# Power_Input_and_Regulators.net
KiCad netlist of a schematic drawn in Altium Designer
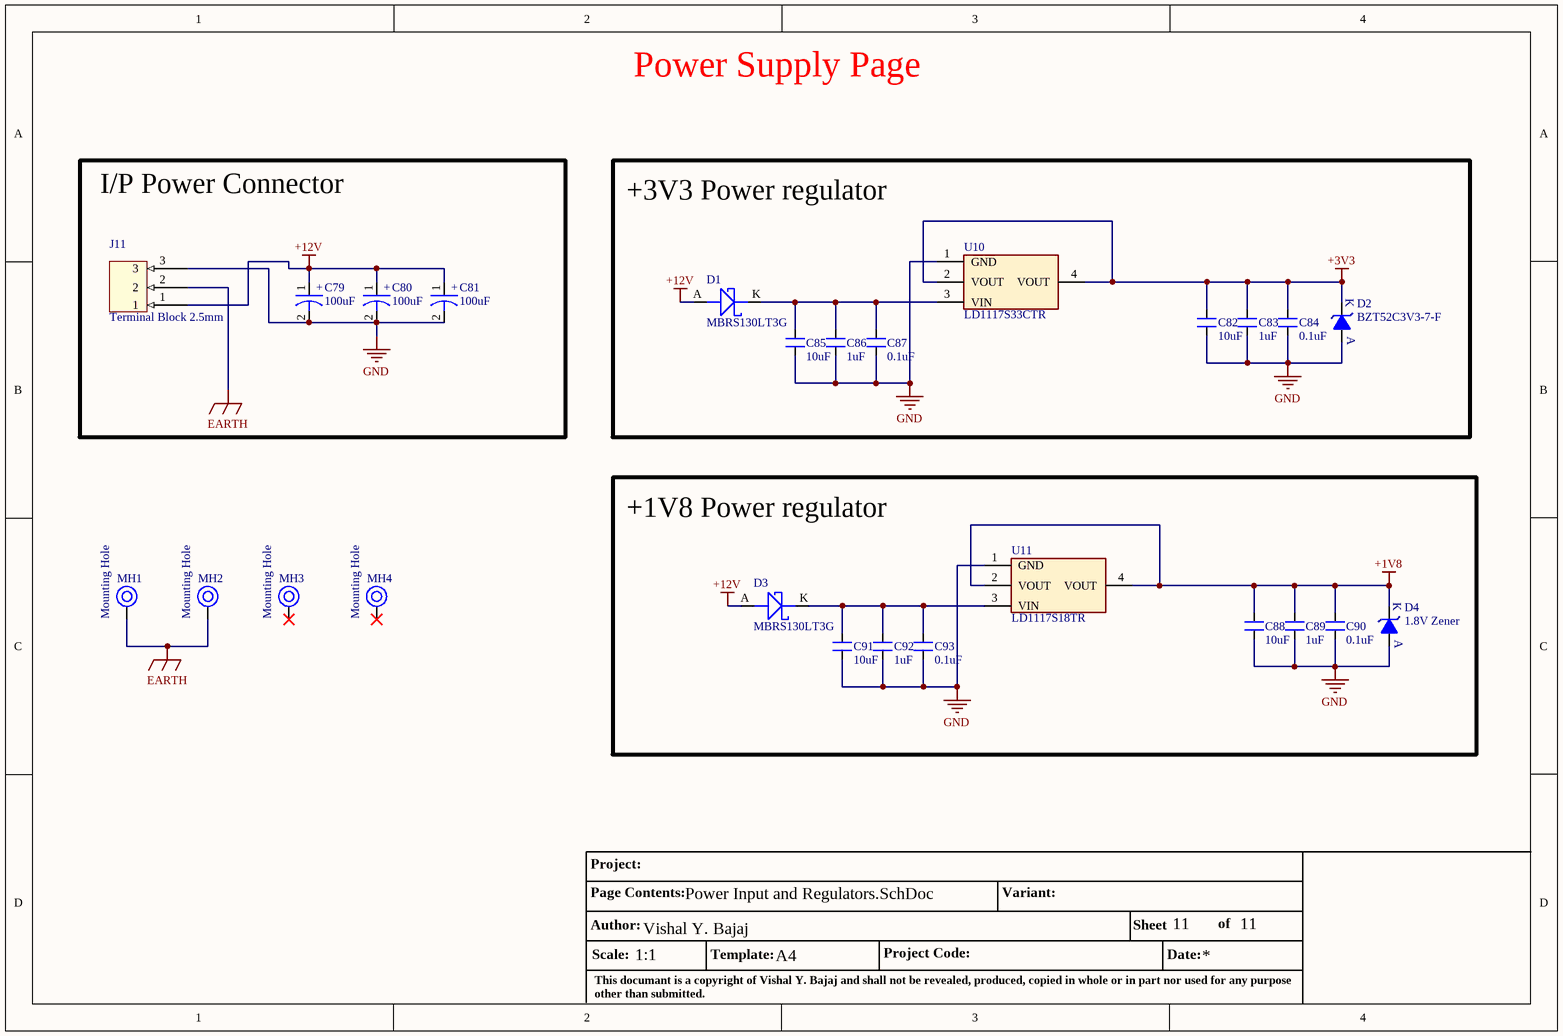
[diagram p0: Power Input and Regulators.SchDoc]

(export (version "E")
  (design (tool "Eeschema 10.0.6"))
  (components
    (comp (ref "C79")
      (value "100uF")
      (footprint "ACAP_P305_D393_H393_RAD")
      (description "100µF 50V Aluminum Polymer Capacitor Radial, Can - SMD 28mOhm 4000 Hrs @ 125°C")
      (fields
        (field (name "MANUFACTURER") "Nichicon")
        (field (name "MANUFACTURER PART NUMBER") "GYA1H101MCQ1GS")
      )
      (libsource (lib "ESTEEMPCBLIB") (part "CAP-P_100uF-50V-20%-RAD"))
    )
    (comp (ref "C80")
      (value "100uF")
      (footprint "ACAP_P305_D393_H393_RAD")
      (description "100µF 50V Aluminum Polymer Capacitor Radial, Can - SMD 28mOhm 4000 Hrs @ 125°C")
      (fields
        (field (name "MANUFACTURER") "Nichicon")
        (field (name "MANUFACTURER PART NUMBER") "GYA1H101MCQ1GS")
      )
      (libsource (lib "ESTEEMPCBLIB") (part "CAP-P_100uF-50V-20%-RAD"))
    )
    (comp (ref "C81")
      (value "100uF")
      (footprint "ACAP_P305_D393_H393_RAD")
      (description "100µF 50V Aluminum Polymer Capacitor Radial, Can - SMD 28mOhm 4000 Hrs @ 125°C")
      (fields
        (field (name "MANUFACTURER") "Nichicon")
        (field (name "MANUFACTURER PART NUMBER") "GYA1H101MCQ1GS")
      )
      (libsource (lib "ESTEEMPCBLIB") (part "CAP-P_100uF-50V-20%-RAD"))
    )
    (comp (ref "C82")
      (value "10uF")
      (footprint "CAP_1206")
      (description "10µF ±10% 50V Ceramic Capacitor X7R 1206 (3216 Metric)")
      (fields
        (field (name "MANUFACTURER") "KEMET")
        (field (name "MANUFACTURER PART NUMBER") "CL31B106KBHNNNE")
      )
      (libsource (lib "ESTEEMPCBLIB") (part "CAP_10uF-50V-10%-1206"))
    )
    (comp (ref "C83")
      (value "1uF")
      (footprint "CAP_0805")
      (description "1µF ±5% 50V Ceramic Capacitor X7R 0805 (2012 Metric)")
      (fields
        (field (name "MANUFACTURER") "Samsung")
        (field (name "MANUFACTURER PART NUMBER") "CC0805JKX7R9BB105")
      )
      (libsource (lib "ESTEEMPCBLIB") (part "CAP_1uF-50V-5%-0805"))
    )
    (comp (ref "C84")
      (value "0.1uF")
      (footprint "CAP_0805")
      (description "0.1µF ±10% 50V Ceramic Capacitor X7R 0805 (2012 Metric)")
      (fields
        (field (name "MANUFACTURER") "Samsung")
        (field (name "MANUFACTURER PART NUMBER") "CL21B104KBCNNNC")
      )
      (libsource (lib "ESTEEMPCBLIB") (part "CAP_0.1uF-50V-10%-0805"))
    )
    (comp (ref "C85")
      (value "10uF")
      (footprint "CAP_1206")
      (description "10µF ±10% 50V Ceramic Capacitor X7R 1206 (3216 Metric)")
      (fields
        (field (name "MANUFACTURER") "KEMET")
        (field (name "MANUFACTURER PART NUMBER") "CL31B106KBHNNNE")
      )
      (libsource (lib "ESTEEMPCBLIB") (part "CAP_10uF-50V-10%-1206"))
    )
    (comp (ref "C86")
      (value "1uF")
      (footprint "CAP_0805")
      (description "1µF ±5% 50V Ceramic Capacitor X7R 0805 (2012 Metric)")
      (fields
        (field (name "MANUFACTURER") "Samsung")
        (field (name "MANUFACTURER PART NUMBER") "CC0805JKX7R9BB105")
      )
      (libsource (lib "ESTEEMPCBLIB") (part "CAP_1uF-50V-5%-0805"))
    )
    (comp (ref "C87")
      (value "0.1uF")
      (footprint "CAP_0805")
      (description "0.1µF ±10% 50V Ceramic Capacitor X7R 0805 (2012 Metric)")
      (fields
        (field (name "MANUFACTURER") "Samsung")
        (field (name "MANUFACTURER PART NUMBER") "CL21B104KBCNNNC")
      )
      (libsource (lib "ESTEEMPCBLIB") (part "CAP_0.1uF-50V-10%-0805"))
    )
    (comp (ref "C88")
      (value "10uF")
      (footprint "CAP_1206")
      (description "10µF ±10% 50V Ceramic Capacitor X7R 1206 (3216 Metric)")
      (fields
        (field (name "MANUFACTURER") "KEMET")
        (field (name "MANUFACTURER PART NUMBER") "CL31B106KBHNNNE")
      )
      (libsource (lib "ESTEEMPCBLIB") (part "CAP_10uF-50V-10%-1206"))
    )
    (comp (ref "C89")
      (value "1uF")
      (footprint "CAP_0805")
      (description "1µF ±5% 50V Ceramic Capacitor X7R 0805 (2012 Metric)")
      (fields
        (field (name "MANUFACTURER") "Samsung")
        (field (name "MANUFACTURER PART NUMBER") "CC0805JKX7R9BB105")
      )
      (libsource (lib "ESTEEMPCBLIB") (part "CAP_1uF-50V-5%-0805"))
    )
    (comp (ref "C90")
      (value "0.1uF")
      (footprint "CAP_0805")
      (description "0.1µF ±10% 50V Ceramic Capacitor X7R 0805 (2012 Metric)")
      (fields
        (field (name "MANUFACTURER") "Samsung")
        (field (name "MANUFACTURER PART NUMBER") "CL21B104KBCNNNC")
      )
      (libsource (lib "ESTEEMPCBLIB") (part "CAP_0.1uF-50V-10%-0805"))
    )
    (comp (ref "C91")
      (value "10uF")
      (footprint "CAP_1206")
      (description "10µF ±10% 50V Ceramic Capacitor X7R 1206 (3216 Metric)")
      (fields
        (field (name "MANUFACTURER") "KEMET")
        (field (name "MANUFACTURER PART NUMBER") "CL31B106KBHNNNE")
      )
      (libsource (lib "ESTEEMPCBLIB") (part "CAP_10uF-50V-10%-1206"))
    )
    (comp (ref "C92")
      (value "1uF")
      (footprint "CAP_0805")
      (description "1µF ±5% 50V Ceramic Capacitor X7R 0805 (2012 Metric)")
      (fields
        (field (name "MANUFACTURER") "Samsung")
        (field (name "MANUFACTURER PART NUMBER") "CC0805JKX7R9BB105")
      )
      (libsource (lib "ESTEEMPCBLIB") (part "CAP_1uF-50V-5%-0805"))
    )
    (comp (ref "C93")
      (value "0.1uF")
      (footprint "CAP_0805")
      (description "0.1µF ±10% 50V Ceramic Capacitor X7R 0805 (2012 Metric)")
      (fields
        (field (name "MANUFACTURER") "Samsung")
        (field (name "MANUFACTURER PART NUMBER") "CL21B104KBCNNNC")
      )
      (libsource (lib "ESTEEMPCBLIB") (part "CAP_0.1uF-50V-10%-0805"))
    )
    (comp (ref "D1")
      (value "MBRS130LT3G")
      (footprint "DIO_SMB_DO-214AA")
      (description "Diode Schottky 30V 2A Surface Mount SMB")
      (fields (field (name "MANUFACTURER") "ON Semiconductor"))
      (libsource (lib "ESTEEMPCBLIB") (part "DIO-S_445mV-30V-2A-SMB"))
    )
    (comp (ref "D2")
      (value "BZT52C3V3-7-F")
      (footprint "DIO_SOD-123")
      (description "Zener Diode 3.3V 500mW ±6% Surface Mount SOD-123")
      (fields (field (name "MANUFACTURER") "Diodes Incorporated"))
      (libsource (lib "ESTEEMPCBLIB") (part "DIO-Z_3.3V-500mW-SOD123"))
    )
    (comp (ref "D3")
      (value "MBRS130LT3G")
      (footprint "DIO_SMB_DO-214AA")
      (description "Diode Schottky 30V 2A Surface Mount SMB")
      (fields (field (name "MANUFACTURER") "ON Semiconductor"))
      (libsource (lib "ESTEEMPCBLIB") (part "DIO-S_445mV-30V-2A-SMB"))
    )
    (comp (ref "D4")
      (value "1.8V Zener")
      (footprint "DIO_DO-213AB_SMD")
      (description "Zener Diode 1.8V 500mW ±5% Surface Mount DO-213AA")
      (libsource (lib "ESTEEMPCBLIB") (part "DIO-Z_1.8V-500mW-DO213AA"))
    )
    (comp (ref "J11")
      (value "Terminal Block 2.5mm")
      (footprint "CON3_100_TB_TH_ST")
      (description "3 Pins, 1 Row 2.54mm Pitch, straight Connector, male")
      (fields
        (field (name "MANUFACTURER PART NUMBER") "1725669")
        (field (name "MANUFACTURER") "Phoenix Contact")
      )
      (libsource (lib "ESTEEMPCBLIB") (part "CON-TB_3X1-100-ST-TH"))
    )
    (comp (ref "MH1")
      (value "Mounting Hole")
      (footprint "MOUNTING")
      (fields (field (name "MANUFACTURER PART NUMBER") "NA"))
      (libsource (lib "ESTEEMPCBLIB") (part "MH_3.5H_6D"))
    )
    (comp (ref "MH2")
      (value "Mounting Hole")
      (footprint "MOUNTING")
      (fields (field (name "MANUFACTURER PART NUMBER") "NA"))
      (libsource (lib "ESTEEMPCBLIB") (part "MH_3.5H_6D"))
    )
    (comp (ref "MH3")
      (value "Mounting Hole")
      (footprint "MOUNTING")
      (fields (field (name "MANUFACTURER PART NUMBER") "NA"))
      (libsource (lib "ESTEEMPCBLIB") (part "MH_3.5H_6D"))
    )
    (comp (ref "MH4")
      (value "Mounting Hole")
      (footprint "MOUNTING")
      (fields (field (name "MANUFACTURER PART NUMBER") "NA"))
      (libsource (lib "ESTEEMPCBLIB") (part "MH_3.5H_6D"))
    )
    (comp (ref "U10")
      (value "LD1117S33CTR")
      (footprint "SOT223_3")
      (description "Linear Voltage Regulator IC 1 Output 800mA SOT-223")
      (fields (field (name "MANUFACTURER") "STMicroelectronics"))
      (libsource (lib "ESTEEMPCBLIB") (part "REG_15V-3.3V-0.9A-12W-SOT223"))
    )
    (comp (ref "U11")
      (value "LD1117S18TR")
      (footprint "SOT223_3")
      (description "LDO Voltage Regulators 1.8V 0.8A Positive")
      (fields (field (name "MANUFACTURER") "STMicroelectronics"))
      (libsource (lib "ESTEEMPCBLIB") (part "REG_15V-1.8V-0.8A-1.4W-SOT223"))
    )
  )
  (nets
    (net (code "1") (name "+1V8") (class "Default")
      (node (ref "C88") (pin "2") (pinfunction "2_2") (pintype "passive"))
      (node (ref "C89") (pin "2") (pinfunction "2_2") (pintype "passive"))
      (node (ref "C90") (pin "2") (pinfunction "2_2") (pintype "passive"))
      (node (ref "D4") (pin "K") (pinfunction "K_K") (pintype "passive"))
      (node (ref "U11") (pin "2") (pinfunction "VOUT_2") (pintype "passive"))
      (node (ref "U11") (pin "4") (pinfunction "VOUT_4") (pintype "passive"))
    )
    (net (code "2") (name "+3V3") (class "Default")
      (node (ref "C82") (pin "2") (pinfunction "2_2") (pintype "passive"))
      (node (ref "C83") (pin "2") (pinfunction "2_2") (pintype "passive"))
      (node (ref "C84") (pin "2") (pinfunction "2_2") (pintype "passive"))
      (node (ref "D2") (pin "K") (pinfunction "K_K") (pintype "passive"))
      (node (ref "U10") (pin "2") (pinfunction "VOUT_2") (pintype "passive"))
      (node (ref "U10") (pin "4") (pinfunction "VOUT_4") (pintype "passive"))
    )
    (net (code "3") (name "+12V") (class "Default")
      (node (ref "C79") (pin "1") (pinfunction "1_1") (pintype "passive"))
      (node (ref "C80") (pin "1") (pinfunction "1_1") (pintype "passive"))
      (node (ref "C81") (pin "1") (pinfunction "1_1") (pintype "passive"))
      (node (ref "D1") (pin "A") (pinfunction "A_A") (pintype "passive"))
      (node (ref "D3") (pin "A") (pinfunction "A_A") (pintype "passive"))
      (node (ref "J11") (pin "1") (pinfunction "1_1") (pintype "input"))
    )
    (net (code "4") (name "EARTH") (class "Default")
      (node (ref "J11") (pin "2") (pinfunction "2_2") (pintype "input"))
      (node (ref "MH1") (pin "1") (pinfunction "1_1") (pintype "passive"))
      (node (ref "MH2") (pin "1") (pinfunction "1_1") (pintype "passive"))
    )
    (net (code "5") (name "GND") (class "Default")
      (node (ref "C79") (pin "2") (pinfunction "2_2") (pintype "passive"))
      (node (ref "C80") (pin "2") (pinfunction "2_2") (pintype "passive"))
      (node (ref "C81") (pin "2") (pinfunction "2_2") (pintype "passive"))
      (node (ref "C82") (pin "1") (pinfunction "1_1") (pintype "passive"))
      (node (ref "C83") (pin "1") (pinfunction "1_1") (pintype "passive"))
      (node (ref "C84") (pin "1") (pinfunction "1_1") (pintype "passive"))
      (node (ref "C85") (pin "1") (pinfunction "1_1") (pintype "passive"))
      (node (ref "C86") (pin "1") (pinfunction "1_1") (pintype "passive"))
      (node (ref "C87") (pin "1") (pinfunction "1_1") (pintype "passive"))
      (node (ref "C88") (pin "1") (pinfunction "1_1") (pintype "passive"))
      (node (ref "C89") (pin "1") (pinfunction "1_1") (pintype "passive"))
      (node (ref "C90") (pin "1") (pinfunction "1_1") (pintype "passive"))
      (node (ref "C91") (pin "1") (pinfunction "1_1") (pintype "passive"))
      (node (ref "C92") (pin "1") (pinfunction "1_1") (pintype "passive"))
      (node (ref "C93") (pin "1") (pinfunction "1_1") (pintype "passive"))
      (node (ref "D2") (pin "A") (pinfunction "A_A") (pintype "passive"))
      (node (ref "D4") (pin "A") (pinfunction "A_A") (pintype "passive"))
      (node (ref "J11") (pin "3") (pinfunction "3_3") (pintype "input"))
      (node (ref "U10") (pin "1") (pinfunction "GND_1") (pintype "passive"))
      (node (ref "U11") (pin "1") (pinfunction "GND_1") (pintype "passive"))
    )
    (net (code "6") (name "Net-(U10-VIN)") (class "Default")
      (node (ref "C85") (pin "2") (pinfunction "2_2") (pintype "passive"))
      (node (ref "C86") (pin "2") (pinfunction "2_2") (pintype "passive"))
      (node (ref "C87") (pin "2") (pinfunction "2_2") (pintype "passive"))
      (node (ref "D1") (pin "K") (pinfunction "K_K") (pintype "passive"))
      (node (ref "U10") (pin "3") (pinfunction "VIN_3") (pintype "passive"))
    )
    (net (code "7") (name "Net-(U11-VIN)") (class "Default")
      (node (ref "C91") (pin "2") (pinfunction "2_2") (pintype "passive"))
      (node (ref "C92") (pin "2") (pinfunction "2_2") (pintype "passive"))
      (node (ref "C93") (pin "2") (pinfunction "2_2") (pintype "passive"))
      (node (ref "D3") (pin "K") (pinfunction "K_K") (pintype "passive"))
      (node (ref "U11") (pin "3") (pinfunction "VIN_3") (pintype "passive"))
    )
    (net (code "8") (name "unconnected-(MH3-Pad1)") (class "Default")
      (node (ref "MH3") (pin "1") (pinfunction "1_1") (pintype "passive+no_connect"))
    )
    (net (code "9") (name "unconnected-(MH4-Pad1)") (class "Default")
      (node (ref "MH4") (pin "1") (pinfunction "1_1") (pintype "passive+no_connect"))
    )
  )
)
